# Sayma_RTM.net
KiCad netlist of a schematic drawn in Altium Designer
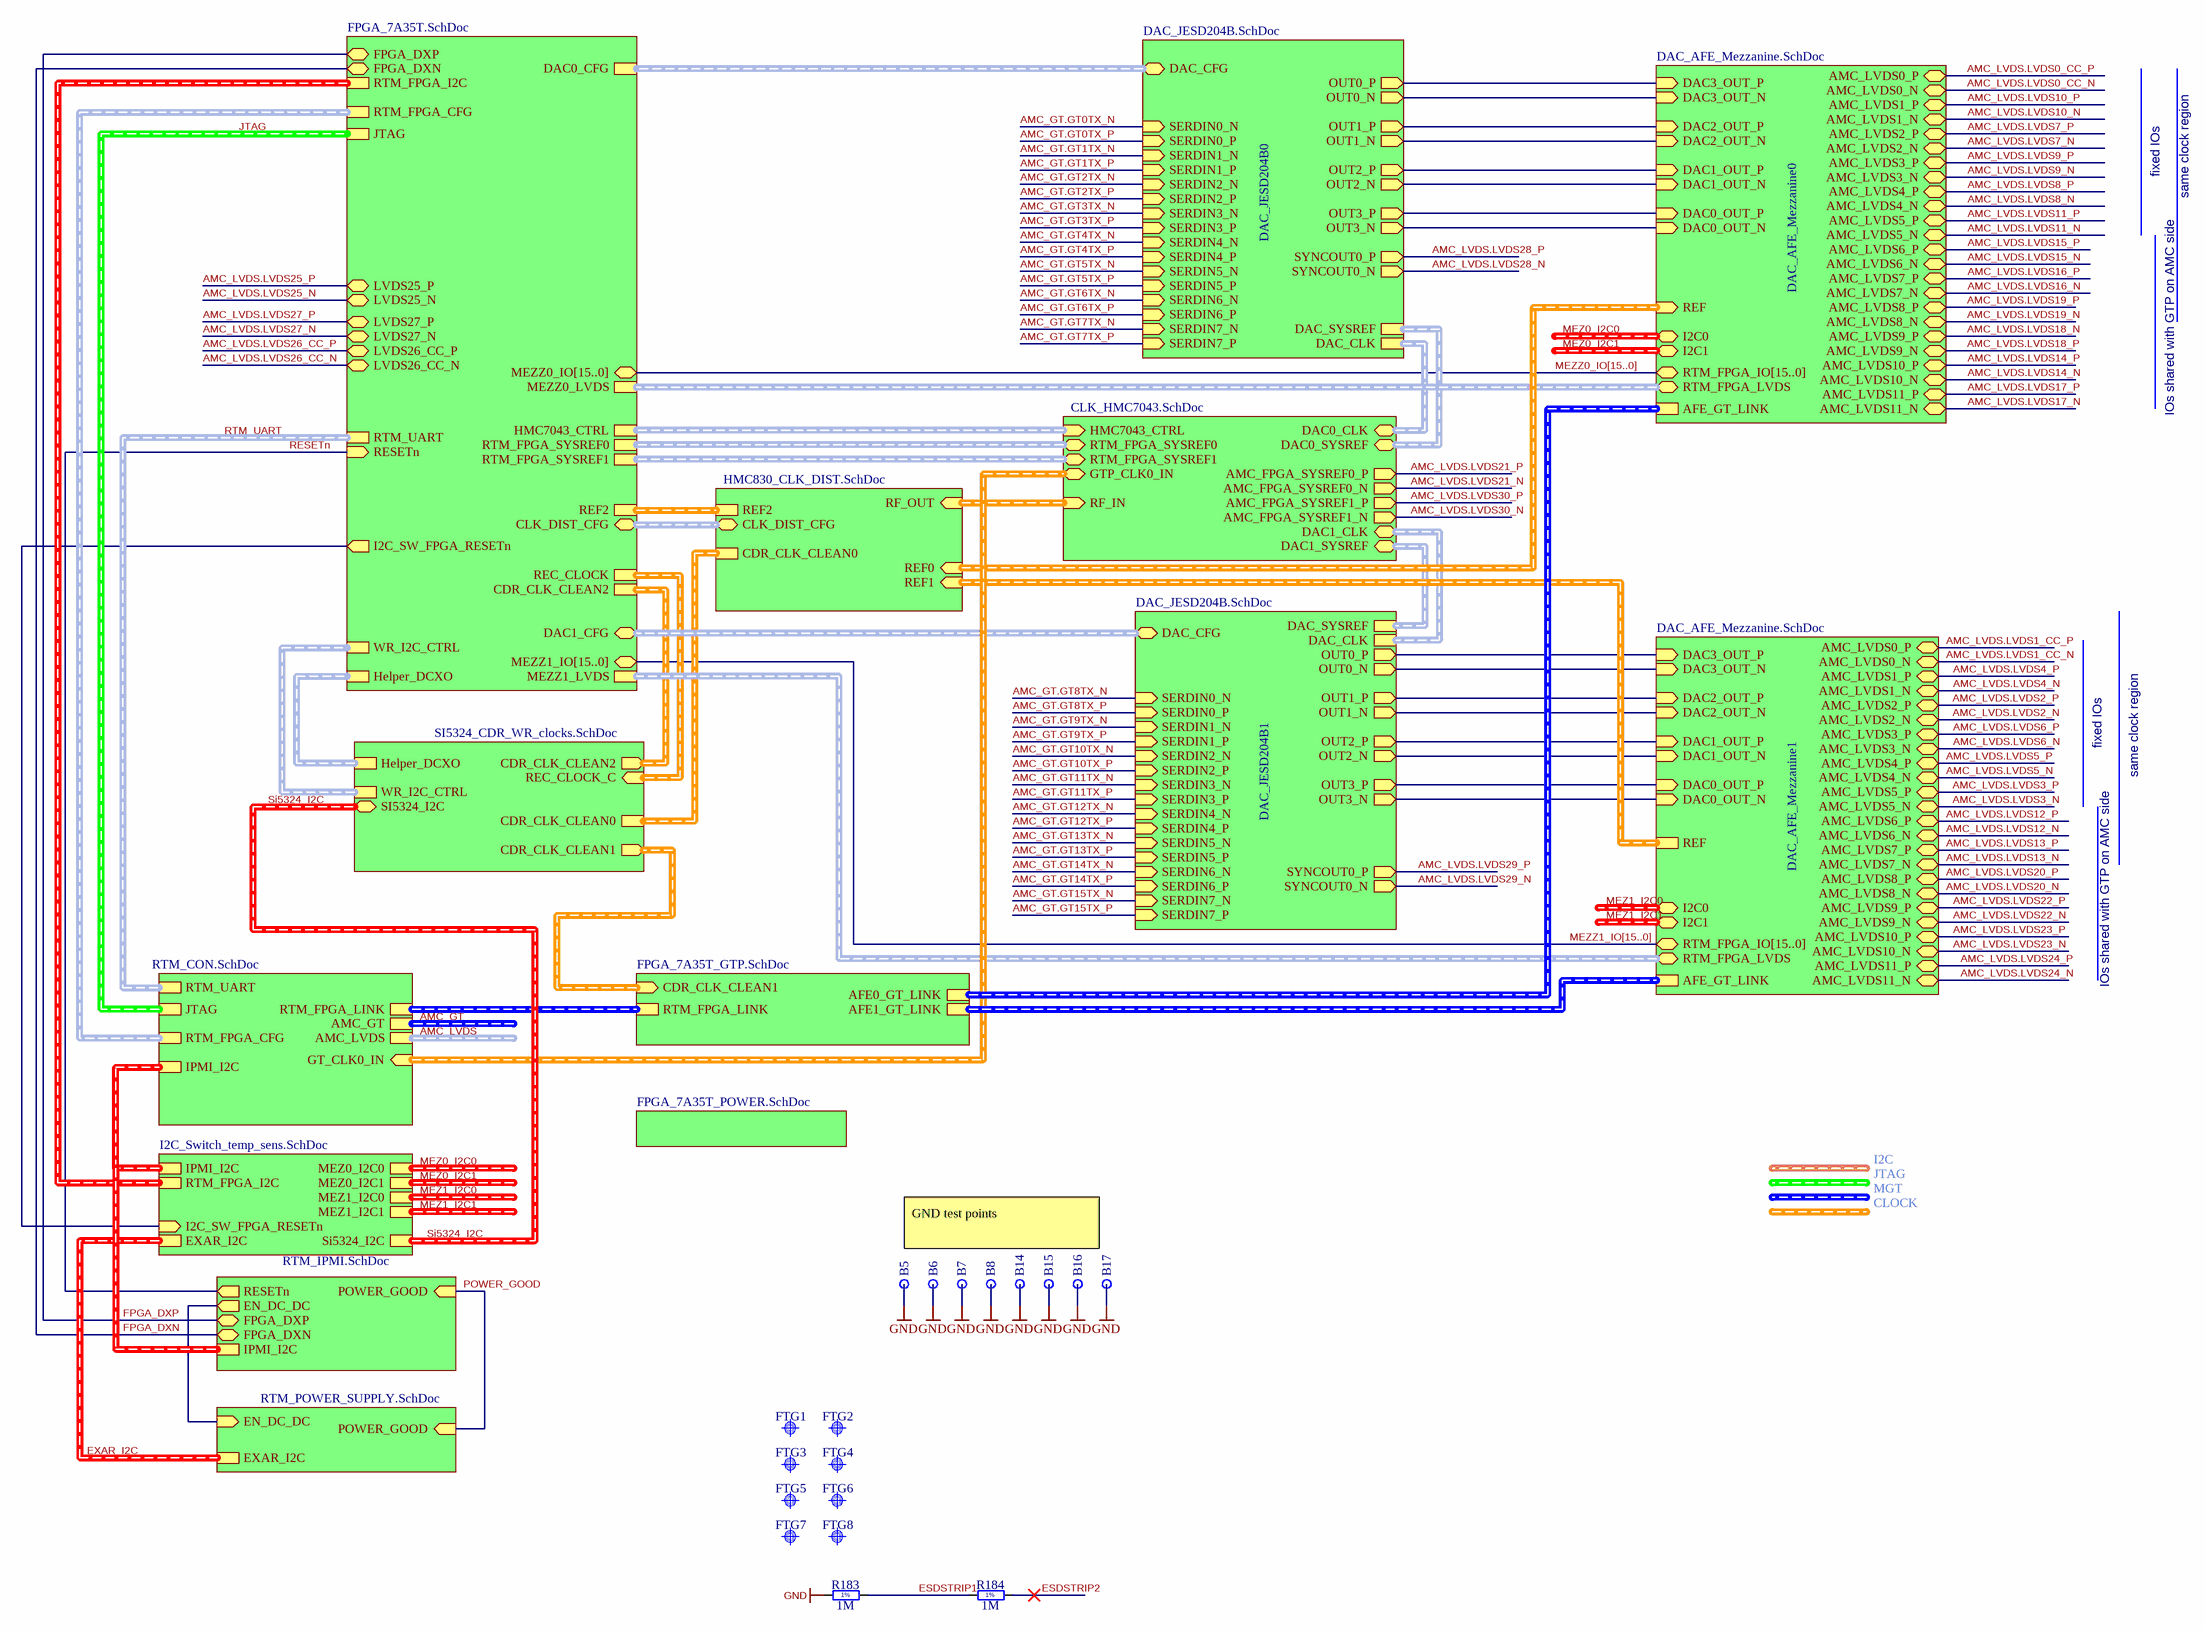
[diagram p0: Sayma_RTM.SchDoc]

(export (version "E")
  (design (tool "Eeschema 10.0.6"))
  (components
    (comp (ref "B5")
      (value "Plated Hole")
      (footprint "c130h80")
      (description "Single Terminal Socket")
      (fields (field (name "PART NUMBER") "PLATED_HOLE0.8_PAD1.3") (field (name "AUTHOR") "CERN DEM JLC"))
      (libsource (lib "Eletro-mechanical") (part "Single Terminal Socket"))
    )
    (comp (ref "B6")
      (value "Plated Hole")
      (footprint "c130h80")
      (description "Single Terminal Socket")
      (fields (field (name "PART NUMBER") "PLATED_HOLE0.8_PAD1.3") (field (name "AUTHOR") "CERN DEM JLC"))
      (libsource (lib "Eletro-mechanical") (part "Single Terminal Socket"))
    )
    (comp (ref "B7")
      (value "Plated Hole")
      (footprint "c130h80")
      (description "Single Terminal Socket")
      (fields (field (name "PART NUMBER") "PLATED_HOLE0.8_PAD1.3") (field (name "AUTHOR") "CERN DEM JLC"))
      (libsource (lib "Eletro-mechanical") (part "Single Terminal Socket"))
    )
    (comp (ref "B8")
      (value "Plated Hole")
      (footprint "c130h80")
      (description "Single Terminal Socket")
      (fields (field (name "PART NUMBER") "PLATED_HOLE0.8_PAD1.3") (field (name "AUTHOR") "CERN DEM JLC"))
      (libsource (lib "Eletro-mechanical") (part "Single Terminal Socket"))
    )
    (comp (ref "B14")
      (value "Plated Hole")
      (footprint "c130h80")
      (description "Single Terminal Socket")
      (fields (field (name "PART NUMBER") "PLATED_HOLE0.8_PAD1.3") (field (name "AUTHOR") "CERN DEM JLC"))
      (libsource (lib "Eletro-mechanical") (part "Single Terminal Socket"))
    )
    (comp (ref "B15")
      (value "Plated Hole")
      (footprint "c130h80")
      (description "Single Terminal Socket")
      (fields (field (name "PART NUMBER") "PLATED_HOLE0.8_PAD1.3") (field (name "AUTHOR") "CERN DEM JLC"))
      (libsource (lib "Eletro-mechanical") (part "Single Terminal Socket"))
    )
    (comp (ref "B16")
      (value "Plated Hole")
      (footprint "c130h80")
      (description "Single Terminal Socket")
      (fields (field (name "PART NUMBER") "PLATED_HOLE0.8_PAD1.3") (field (name "AUTHOR") "CERN DEM JLC"))
      (libsource (lib "Eletro-mechanical") (part "Single Terminal Socket"))
    )
    (comp (ref "B17")
      (value "Plated Hole")
      (footprint "c130h80")
      (description "Single Terminal Socket")
      (fields (field (name "PART NUMBER") "PLATED_HOLE0.8_PAD1.3") (field (name "AUTHOR") "CERN DEM JLC"))
      (libsource (lib "Eletro-mechanical") (part "Single Terminal Socket"))
    )
    (comp (ref "FTG1")
      (value "Use only in PCB")
      (footprint "FIDUCIAL_TOP_C100-200")
      (description "Fiducial Target")
      (fields (field (name "PART NUMBER") "FIDUCIAL_TARGET_C100-200") (field (name "AUTHOR") "CERN DEM JLC"))
      (libsource (lib "Eletro-mechanical") (part "Fiducial Target"))
    )
    (comp (ref "FTG2")
      (value "Use only in PCB")
      (footprint "FIDUCIAL_TOP_S100-200")
      (description "Fiducial Target")
      (fields (field (name "PART NUMBER") "FIDUCIAL_TARGET_S100-200") (field (name "AUTHOR") "CERN DEM JLC"))
      (libsource (lib "Eletro-mechanical") (part "Fiducial Target"))
    )
    (comp (ref "FTG3")
      (value "Use only in PCB")
      (footprint "FIDUCIAL_TOP_C100-200")
      (description "Fiducial Target")
      (fields (field (name "PART NUMBER") "FIDUCIAL_TARGET_C100-200") (field (name "AUTHOR") "CERN DEM JLC"))
      (libsource (lib "Eletro-mechanical") (part "Fiducial Target"))
    )
    (comp (ref "FTG4")
      (value "Use only in PCB")
      (footprint "FIDUCIAL_TOP_S100-200")
      (description "Fiducial Target")
      (fields (field (name "PART NUMBER") "FIDUCIAL_TARGET_S100-200") (field (name "AUTHOR") "CERN DEM JLC"))
      (libsource (lib "Eletro-mechanical") (part "Fiducial Target"))
    )
    (comp (ref "FTG5")
      (value "Use only in PCB")
      (footprint "FIDUCIAL_TOP_C100-200")
      (description "Fiducial Target")
      (fields (field (name "PART NUMBER") "FIDUCIAL_TARGET_C100-200") (field (name "AUTHOR") "CERN DEM JLC"))
      (libsource (lib "Eletro-mechanical") (part "Fiducial Target"))
    )
    (comp (ref "FTG6")
      (value "Use only in PCB")
      (footprint "FIDUCIAL_TOP_S100-200")
      (description "Fiducial Target")
      (fields (field (name "PART NUMBER") "FIDUCIAL_TARGET_S100-200") (field (name "AUTHOR") "CERN DEM JLC"))
      (libsource (lib "Eletro-mechanical") (part "Fiducial Target"))
    )
    (comp (ref "FTG7")
      (value "Use only in PCB")
      (footprint "FIDUCIAL_TOP_C100-200")
      (description "Fiducial Target")
      (fields (field (name "PART NUMBER") "FIDUCIAL_TARGET_C100-200") (field (name "AUTHOR") "CERN DEM JLC"))
      (libsource (lib "Eletro-mechanical") (part "Fiducial Target"))
    )
    (comp (ref "FTG8")
      (value "Use only in PCB")
      (footprint "FIDUCIAL_TOP_S100-200")
      (description "Fiducial Target")
      (fields (field (name "PART NUMBER") "FIDUCIAL_TARGET_S100-200") (field (name "AUTHOR") "CERN DEM JLC"))
      (libsource (lib "Eletro-mechanical") (part "Fiducial Target"))
    )
    (comp (ref "R183")
      (value "1M")
      (footprint "RESC5025X65N")
      (description "Resistor - 1%")
      (fields
        (field (name "MANUFACTURER PART NUMBER") "R2010_1M_1%_0.5W_200PPM")
        (field (name "MANUFACTURER") "GENERIC")
        (field (name "AUTHOR") "CERN DEM JLC")
      )
      (libsource (lib "Resistors") (part "Resistor - 1%"))
    )
    (comp (ref "R184")
      (value "1M")
      (footprint "RESC5025X65N")
      (description "Resistor - 1%")
      (fields
        (field (name "MANUFACTURER PART NUMBER") "R2010_1M_1%_0.5W_200PPM")
        (field (name "MANUFACTURER") "GENERIC")
        (field (name "AUTHOR") "CERN DEM JLC")
      )
      (libsource (lib "Resistors") (part "Resistor - 1%"))
    )
  )
  (nets
    (net (code "150") (name "/ESDSTRIP1") (class "Default")
      (node (ref "R183") (pin "2") (pinfunction "2_2") (pintype "passive"))
      (node (ref "R184") (pin "1") (pinfunction "1_1") (pintype "passive"))
    )
    (net (code "151") (name "/ESDSTRIP2") (class "Default")
      (node (ref "R184") (pin "2") (pinfunction "2_2") (pintype "passive"))
    )
    (net (code "202") (name "GND") (class "Default")
      (node (ref "B14") (pin "1") (pinfunction "1_1") (pintype "bidirectional"))
      (node (ref "B15") (pin "1") (pinfunction "1_1") (pintype "bidirectional"))
      (node (ref "B16") (pin "1") (pinfunction "1_1") (pintype "bidirectional"))
      (node (ref "B17") (pin "1") (pinfunction "1_1") (pintype "bidirectional"))
      (node (ref "B5") (pin "1") (pinfunction "1_1") (pintype "bidirectional"))
      (node (ref "B6") (pin "1") (pinfunction "1_1") (pintype "bidirectional"))
      (node (ref "B7") (pin "1") (pinfunction "1_1") (pintype "bidirectional"))
      (node (ref "B8") (pin "1") (pinfunction "1_1") (pintype "bidirectional"))
      (node (ref "R183") (pin "1") (pinfunction "1_1") (pintype "passive"))
    )
  )
)
